# uc3906_charger_2.net
KiCad netlist of a schematic drawn in EAGLE
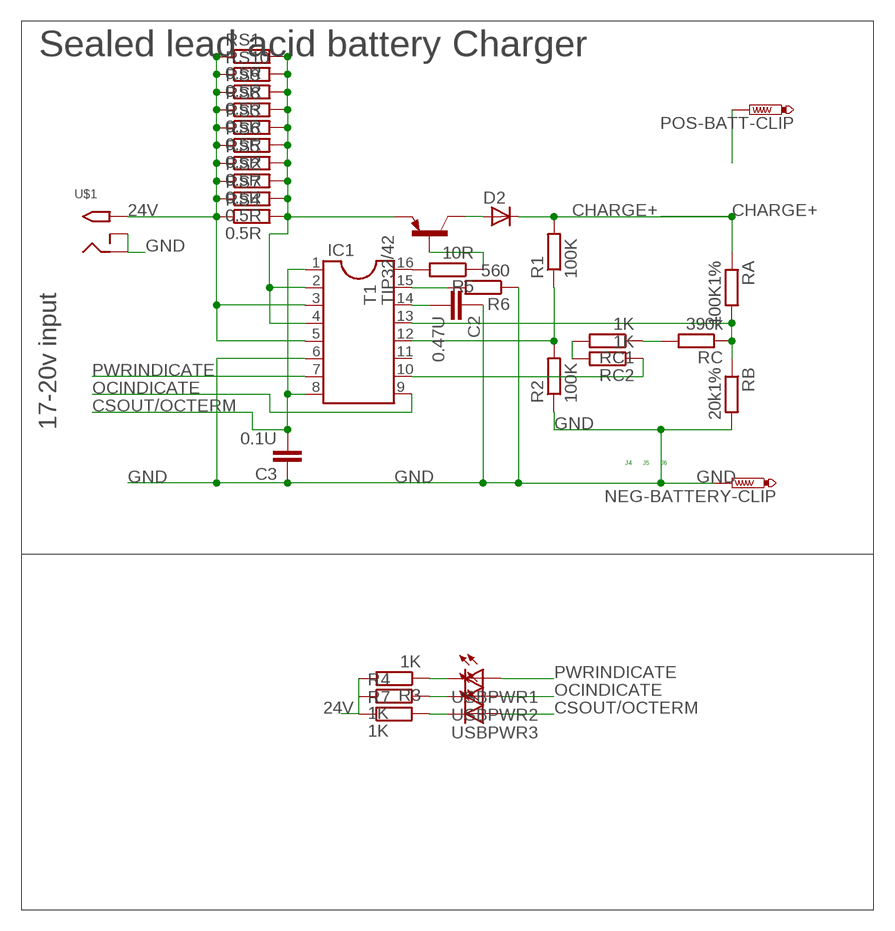
[diagram p0: schematic, sheet 1]

(export (version "E")
  (design (tool "Eeschema 10.0.6"))
  (components
    (comp (ref "C2")
      (value "0.47U")
      (footprint "eagle-import:C1206")
      (libsource (lib "eagle-import") (part "C-EUC1206"))
    )
    (comp (ref "C3")
      (value "0.1U")
      (footprint "eagle-import:C1206")
      (libsource (lib "eagle-import") (part "C-EUC1206"))
    )
    (comp (ref "D2")
      (value "D-MLL-41")
      (footprint "eagle-import:MELF-MLL41")
      (libsource (lib "eagle-import") (part "D-MLL-41"))
    )
    (comp (ref "IC1")
      (value "DIL16")
      (footprint "eagle-import:DIL16")
      (libsource (lib "eagle-import") (part "DIL16"))
    )
    (comp (ref "NEG-BATTERY-CLIP")
      (value "PTR1PAD1-20Y")
      (footprint "eagle-import:P1-20Y")
      (libsource (lib "eagle-import") (part "PTR1PAD1-20Y"))
    )
    (comp (ref "POS-BATT-CLIP")
      (value "PTR1PAD1-20Y")
      (footprint "eagle-import:P1-20Y")
      (libsource (lib "eagle-import") (part "PTR1PAD1-20Y"))
    )
    (comp (ref "R1")
      (value "100K")
      (footprint "eagle-import:M1206")
      (libsource (lib "eagle-import") (part "R-EU_M1206"))
    )
    (comp (ref "R2")
      (value "100K")
      (footprint "eagle-import:M1206")
      (libsource (lib "eagle-import") (part "R-EU_M1206"))
    )
    (comp (ref "R3")
      (value "1K")
      (footprint "eagle-import:M1206")
      (libsource (lib "eagle-import") (part "R-EU_M1206"))
    )
    (comp (ref "R4")
      (value "1K")
      (footprint "eagle-import:M1206")
      (libsource (lib "eagle-import") (part "R-EU_M1206"))
    )
    (comp (ref "R5")
      (value "10R")
      (footprint "eagle-import:M1206")
      (libsource (lib "eagle-import") (part "R-EU_M1206"))
    )
    (comp (ref "R6")
      (value "560")
      (footprint "eagle-import:M1206")
      (libsource (lib "eagle-import") (part "R-EU_M1206"))
    )
    (comp (ref "R7")
      (value "1K")
      (footprint "eagle-import:M1206")
      (libsource (lib "eagle-import") (part "R-EU_M1206"))
    )
    (comp (ref "RA")
      (value "100K1%")
      (footprint "eagle-import:M1206")
      (libsource (lib "eagle-import") (part "R-EU_M1206"))
    )
    (comp (ref "RB")
      (value "20k1%")
      (footprint "eagle-import:M1206")
      (libsource (lib "eagle-import") (part "R-EU_M1206"))
    )
    (comp (ref "RC")
      (value "390k")
      (footprint "eagle-import:M1206")
      (libsource (lib "eagle-import") (part "R-EU_M1206"))
    )
    (comp (ref "RC1")
      (value "1K")
      (footprint "eagle-import:M1206")
      (libsource (lib "eagle-import") (part "R-EU_M1206"))
    )
    (comp (ref "RC2")
      (value "1K")
      (footprint "eagle-import:M1206")
      (libsource (lib "eagle-import") (part "R-EU_M1206"))
    )
    (comp (ref "RS1")
      (value "0.5R")
      (footprint "eagle-import:R2512")
      (libsource (lib "eagle-import") (part "resistor_R-EU_R2512"))
    )
    (comp (ref "RS2")
      (value "0.5R")
      (footprint "eagle-import:0617V")
      (libsource (lib "eagle-import") (part "resistor_R-EU_0617/5V"))
    )
    (comp (ref "RS3")
      (value "0.5R")
      (footprint "eagle-import:R2512")
      (libsource (lib "eagle-import") (part "resistor_R-EU_R2512"))
    )
    (comp (ref "RS4")
      (value "0.5R")
      (footprint "eagle-import:0617V")
      (libsource (lib "eagle-import") (part "resistor_R-EU_0617/5V"))
    )
    (comp (ref "RS5")
      (value "0.5R")
      (footprint "eagle-import:R2512")
      (libsource (lib "eagle-import") (part "resistor_R-EU_R2512"))
    )
    (comp (ref "RS6")
      (value "0.5R")
      (footprint "eagle-import:0617V")
      (libsource (lib "eagle-import") (part "resistor_R-EU_0617/5V"))
    )
    (comp (ref "RS7")
      (value "0.5R")
      (footprint "eagle-import:R2512")
      (libsource (lib "eagle-import") (part "resistor_R-EU_R2512"))
    )
    (comp (ref "RS8")
      (value "0.5R")
      (footprint "eagle-import:0617V")
      (libsource (lib "eagle-import") (part "resistor_R-EU_0617/5V"))
    )
    (comp (ref "RS9")
      (value "0.5R")
      (footprint "eagle-import:R2512")
      (libsource (lib "eagle-import") (part "resistor_R-EU_R2512"))
    )
    (comp (ref "RS10")
      (value "0.5R")
      (footprint "eagle-import:R2512")
      (libsource (lib "eagle-import") (part "resistor_R-EU_R2512"))
    )
    (comp (ref "T1")
      (value "TIP32/42")
      (footprint "eagle-import:TO220")
      (libsource (lib "eagle-import") (part "TIP32C"))
    )
    (comp (ref "U$1")
      (value "2.1MMJACKTHM")
      (footprint "eagle-import:PJ-102A")
      (libsource (lib "eagle-import") (part "2.1MMJACKTHM"))
    )
    (comp (ref "USBPWR1")
      (value "LEDCHIPLED_1206")
      (footprint "eagle-import:CHIPLED_1206")
      (libsource (lib "eagle-import") (part "LEDCHIPLED_1206"))
    )
    (comp (ref "USBPWR2")
      (value "LEDCHIPLED_1206")
      (footprint "eagle-import:CHIPLED_1206")
      (libsource (lib "eagle-import") (part "LEDCHIPLED_1206"))
    )
    (comp (ref "USBPWR3")
      (value "LEDCHIPLED_1206")
      (footprint "eagle-import:CHIPLED_1206")
      (libsource (lib "eagle-import") (part "LEDCHIPLED_1206"))
    )
  )
  (nets
    (net (code "1") (name "/24V") (class "Default")
      (node (ref "IC1") (pin "3") (pinfunction "3_3") (pintype "passive"))
      (node (ref "IC1") (pin "5") (pinfunction "5_5") (pintype "passive"))
      (node (ref "R3") (pin "2") (pinfunction "2_2") (pintype "passive"))
      (node (ref "R4") (pin "1") (pinfunction "1_1") (pintype "passive"))
      (node (ref "R7") (pin "1") (pinfunction "1_1") (pintype "passive"))
      (node (ref "RS1") (pin "1") (pinfunction "1_1") (pintype "passive"))
      (node (ref "RS10") (pin "1") (pinfunction "1_1") (pintype "passive"))
      (node (ref "RS2") (pin "1") (pinfunction "1_1") (pintype "passive"))
      (node (ref "RS3") (pin "1") (pinfunction "1_1") (pintype "passive"))
      (node (ref "RS4") (pin "1") (pinfunction "1_1") (pintype "passive"))
      (node (ref "RS5") (pin "1") (pinfunction "1_1") (pintype "passive"))
      (node (ref "RS6") (pin "1") (pinfunction "1_1") (pintype "passive"))
      (node (ref "RS7") (pin "1") (pinfunction "1_1") (pintype "passive"))
      (node (ref "RS8") (pin "1") (pinfunction "1_1") (pintype "passive"))
      (node (ref "RS9") (pin "1") (pinfunction "1_1") (pintype "passive"))
      (node (ref "U$1") (pin "TIP") (pinfunction "TIP_TIP") (pintype "bidirectional"))
    )
    (net (code "2") (name "/CHARGE+") (class "Default")
      (node (ref "D2") (pin "1") (pinfunction "C_1") (pintype "passive"))
      (node (ref "POS-BATT-CLIP") (pin "TP") (pinfunction "TP_TP") (pintype "input"))
      (node (ref "R1") (pin "2") (pinfunction "2_2") (pintype "passive"))
      (node (ref "RA") (pin "1") (pinfunction "1_1") (pintype "passive"))
    )
    (net (code "3") (name "/CSOUT{slash}OCTERM") (class "Default")
      (node (ref "C3") (pin "2") (pinfunction "2_2") (pintype "passive"))
      (node (ref "IC1") (pin "1") (pinfunction "1_1") (pintype "passive"))
      (node (ref "IC1") (pin "8") (pinfunction "8_8") (pintype "passive"))
      (node (ref "USBPWR3") (pin "A") (pinfunction "A_A") (pintype "passive"))
    )
    (net (code "4") (name "/GND") (class "Default")
      (node (ref "C2") (pin "1") (pinfunction "1_1") (pintype "passive"))
      (node (ref "C3") (pin "1") (pinfunction "1_1") (pintype "passive"))
      (node (ref "IC1") (pin "6") (pinfunction "6_6") (pintype "passive"))
      (node (ref "NEG-BATTERY-CLIP") (pin "TP") (pinfunction "TP_TP") (pintype "input"))
      (node (ref "R2") (pin "1") (pinfunction "1_1") (pintype "passive"))
      (node (ref "R6") (pin "1") (pinfunction "1_1") (pintype "passive"))
      (node (ref "RB") (pin "2") (pinfunction "2_2") (pintype "passive"))
      (node (ref "U$1") (pin "RING") (pinfunction "RING_RING") (pintype "bidirectional"))
      (node (ref "U$1") (pin "RING_SW") (pinfunction "RING_SW_RING_SW") (pintype "bidirectional"))
    )
    (net (code "5") (name "/OCINDICATE") (class "Default")
      (node (ref "IC1") (pin "9") (pinfunction "9_9") (pintype "passive"))
      (node (ref "USBPWR2") (pin "A") (pinfunction "A_A") (pintype "passive"))
    )
    (net (code "6") (name "/PWRINDICATE") (class "Default")
      (node (ref "IC1") (pin "7") (pinfunction "7_7") (pintype "passive"))
      (node (ref "USBPWR1") (pin "A") (pinfunction "A_A") (pintype "passive"))
    )
    (net (code "7") (name "Net-(C2-Pad2)") (class "Default")
      (node (ref "C2") (pin "2") (pinfunction "2_2") (pintype "passive"))
      (node (ref "IC1") (pin "14") (pinfunction "14_14") (pintype "passive"))
    )
    (net (code "8") (name "Net-(D2-A)") (class "Default")
      (node (ref "D2") (pin "2") (pinfunction "A_2") (pintype "passive"))
      (node (ref "T1") (pin "2") (pinfunction "C_2") (pintype "passive"))
    )
    (net (code "9") (name "Net-(IC1-Pad10)") (class "Default")
      (node (ref "IC1") (pin "10") (pinfunction "10_10") (pintype "passive"))
      (node (ref "RC2") (pin "1") (pinfunction "1_1") (pintype "passive"))
    )
    (net (code "10") (name "Net-(IC1-Pad12)") (class "Default")
      (node (ref "IC1") (pin "12") (pinfunction "12_12") (pintype "passive"))
      (node (ref "R1") (pin "1") (pinfunction "1_1") (pintype "passive"))
      (node (ref "R2") (pin "2") (pinfunction "2_2") (pintype "passive"))
    )
    (net (code "11") (name "Net-(IC1-Pad13)") (class "Default")
      (node (ref "IC1") (pin "13") (pinfunction "13_13") (pintype "passive"))
      (node (ref "RA") (pin "2") (pinfunction "2_2") (pintype "passive"))
      (node (ref "RB") (pin "1") (pinfunction "1_1") (pintype "passive"))
      (node (ref "RC") (pin "1") (pinfunction "1_1") (pintype "passive"))
    )
    (net (code "12") (name "Net-(IC1-Pad15)") (class "Default")
      (node (ref "IC1") (pin "15") (pinfunction "15_15") (pintype "passive"))
      (node (ref "R6") (pin "2") (pinfunction "2_2") (pintype "passive"))
    )
    (net (code "13") (name "Net-(IC1-Pad16)") (class "Default")
      (node (ref "IC1") (pin "16") (pinfunction "16_16") (pintype "passive"))
      (node (ref "R5") (pin "2") (pinfunction "2_2") (pintype "passive"))
    )
    (net (code "14") (name "Net-(R3-Pad1)") (class "Default")
      (node (ref "R3") (pin "1") (pinfunction "1_1") (pintype "passive"))
      (node (ref "USBPWR1") (pin "C") (pinfunction "C_C") (pintype "passive"))
    )
    (net (code "15") (name "Net-(R4-Pad2)") (class "Default")
      (node (ref "R4") (pin "2") (pinfunction "2_2") (pintype "passive"))
      (node (ref "USBPWR2") (pin "C") (pinfunction "C_C") (pintype "passive"))
    )
    (net (code "16") (name "Net-(R7-Pad2)") (class "Default")
      (node (ref "R7") (pin "2") (pinfunction "2_2") (pintype "passive"))
      (node (ref "USBPWR3") (pin "C") (pinfunction "C_C") (pintype "passive"))
    )
    (net (code "17") (name "Net-(RC-Pad2)") (class "Default")
      (node (ref "RC") (pin "2") (pinfunction "2_2") (pintype "passive"))
      (node (ref "RC1") (pin "1") (pinfunction "1_1") (pintype "passive"))
    )
    (net (code "18") (name "Net-(RC1-Pad2)") (class "Default")
      (node (ref "RC1") (pin "2") (pinfunction "2_2") (pintype "passive"))
      (node (ref "RC2") (pin "2") (pinfunction "2_2") (pintype "passive"))
    )
    (net (code "19") (name "Net-(T1-B)") (class "Default")
      (node (ref "R5") (pin "1") (pinfunction "1_1") (pintype "passive"))
      (node (ref "T1") (pin "1") (pinfunction "B_1") (pintype "passive"))
    )
    (net (code "20") (name "Net-(T1-E)") (class "Default")
      (node (ref "IC1") (pin "2") (pinfunction "2_2") (pintype "passive"))
      (node (ref "IC1") (pin "4") (pinfunction "4_4") (pintype "passive"))
      (node (ref "RS1") (pin "2") (pinfunction "2_2") (pintype "passive"))
      (node (ref "RS10") (pin "2") (pinfunction "2_2") (pintype "passive"))
      (node (ref "RS2") (pin "2") (pinfunction "2_2") (pintype "passive"))
      (node (ref "RS3") (pin "2") (pinfunction "2_2") (pintype "passive"))
      (node (ref "RS4") (pin "2") (pinfunction "2_2") (pintype "passive"))
      (node (ref "RS5") (pin "2") (pinfunction "2_2") (pintype "passive"))
      (node (ref "RS6") (pin "2") (pinfunction "2_2") (pintype "passive"))
      (node (ref "RS7") (pin "2") (pinfunction "2_2") (pintype "passive"))
      (node (ref "RS8") (pin "2") (pinfunction "2_2") (pintype "passive"))
      (node (ref "RS9") (pin "2") (pinfunction "2_2") (pintype "passive"))
      (node (ref "T1") (pin "3") (pinfunction "E_3") (pintype "passive"))
    )
    (net (code "21") (name "unconnected-(IC1-Pad11)") (class "Default")
      (node (ref "IC1") (pin "11") (pinfunction "11_11") (pintype "passive"))
    )
  )
)
